# LiPo_Charger.net
KiCad netlist of a schematic drawn in Altium Designer
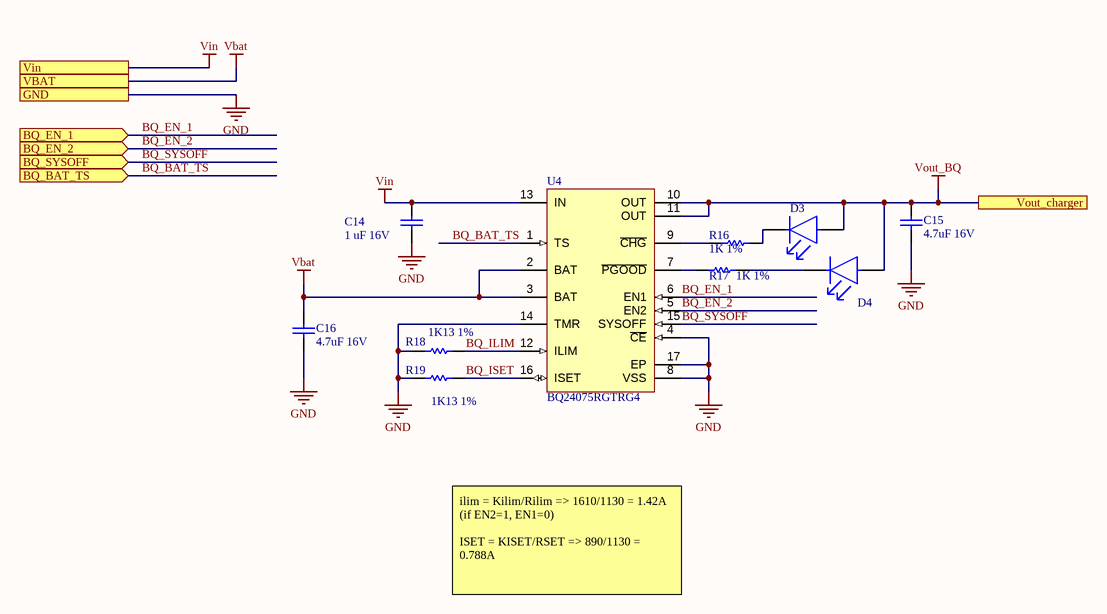
[diagram p0: LiPo_Charger.SchDoc]

(export (version "E")
  (design (tool "Eeschema 10.0.6"))
  (components
    (comp (ref "C14")
      (value "1 uF 16V")
      (footprint "CAPC1608X90X35ML15T15")
      (description "0603YC105JAT2A")
      (fields (field (name "MANUFACTURER") "AVX Interconnect / Elco"))
      (libsource (lib "Altium Content Vault") (part "CAP"))
    )
    (comp (ref "C15")
      (value "4.7uF 16V")
      (footprint "CAPC0805(2012)145_N")
      (description "CAP 4.7uF 16V -20% to +80% 0805 (2012 Metric) Thickness 1.45mm SMD")
      (fields (field (name "TOLERANCE") "-20% to +80%"))
      (libsource (lib "Altium Content Vault") (part "CAP"))
    )
    (comp (ref "C16")
      (value "4.7uF 16V")
      (footprint "CAPC0805(2012)145_N")
      (description "CAP 4.7uF 16V -20% to +80% 0805 (2012 Metric) Thickness 1.45mm SMD")
      (fields (field (name "TOLERANCE") "-20% to +80%"))
      (libsource (lib "Altium Content Vault") (part "CAP"))
    )
    (comp (ref "D3")
      (value "LTST-C170CKT")
      (footprint "FP-LTST-C170CKT-MFG")
      (description "LED RED CLEAR SMD")
      (fields (field (name "VOLTAGE") "5V"))
      (libsource (lib "Altium Content Vault") (part "8706943c75ba83719d021d2fdc84c58"))
    )
    (comp (ref "D4")
      (value "LTST-C170GKT")
      (footprint "FP-LTST-C170GKT-MFG")
      (description "LED GREEN CLEAR SMD")
      (fields (field (name "VOLTAGE") "5V"))
      (libsource (lib "Altium Content Vault") (part "8706943c75ba83719d021d2fdc84c58"))
    )
    (comp (ref "R16")
      (value "1K 1%")
      (footprint "RESC1609X50X30LL10T20")
      (description "CRCW06031K00FKEB")
      (fields (field (name "MANUFACTURER") "Vishay Dale"))
      (libsource (lib "Altium Content Vault") (part "RES"))
    )
    (comp (ref "R17")
      (value "1K 1%")
      (footprint "RESC1609X50X30LL10T20")
      (description "CRCW06031K00FKEB")
      (fields (field (name "MANUFACTURER") "Vishay Dale"))
      (libsource (lib "Altium Content Vault") (part "RES"))
    )
    (comp (ref "R18")
      (value "1K13 1%")
      (footprint "RESC0603(1608)_N")
      (description "1K13 0.1W 1% 0603 (1608 Metric)  SMD")
      (fields (field (name "POWER") "0.1 W") (field (name "TOLERANCE") "1 %"))
      (libsource (lib "Altium Content Vault") (part "RES"))
    )
    (comp (ref "R19")
      (value "1K13 1%")
      (footprint "RESC0603(1608)_N")
      (description "1K13 0.1W 1% 0603 (1608 Metric)  SMD")
      (fields (field (name "POWER") "0.1 W") (field (name "TOLERANCE") "1 %"))
      (libsource (lib "Altium Content Vault") (part "RES"))
    )
    (comp (ref "U4")
      (value "BQ24075RGTRG4")
      (footprint "RGT16-1700X1700TP")
      (fields (field (name "MANUFACTURER") "Texas Instruments"))
      (libsource (lib "Altium Content Vault") (part "TI-BQ24075RGT16-1700X1700TP"))
    )
  )
  (nets
    (net (code "1") (name "/BQ_BAT_TS") (class "Default")
      (node (ref "U4") (pin "1") (pinfunction "TS_1") (pintype "input"))
    )
    (net (code "2") (name "/BQ_EN_1") (class "Default")
      (node (ref "U4") (pin "6") (pinfunction "EN1_6") (pintype "input"))
    )
    (net (code "3") (name "/BQ_EN_2") (class "Default")
      (node (ref "U4") (pin "5") (pinfunction "EN2_5") (pintype "input"))
    )
    (net (code "4") (name "/BQ_ILIM") (class "Default")
      (node (ref "R18") (pin "2") (pinfunction "2_2") (pintype "passive"))
      (node (ref "U4") (pin "12") (pinfunction "ILIM_12") (pintype "input"))
    )
    (net (code "5") (name "/BQ_ISET") (class "Default")
      (node (ref "R19") (pin "2") (pinfunction "2_2") (pintype "passive"))
      (node (ref "U4") (pin "16") (pinfunction "ISET_16") (pintype "bidirectional"))
    )
    (net (code "6") (name "/BQ_SYSOFF") (class "Default")
      (node (ref "U4") (pin "15") (pinfunction "SYSOFF_15") (pintype "input"))
    )
    (net (code "7") (name "GND") (class "Default")
      (node (ref "C14") (pin "1") (pinfunction "1_1") (pintype "passive"))
      (node (ref "C15") (pin "1") (pinfunction "1_1") (pintype "passive"))
      (node (ref "C16") (pin "2") (pinfunction "2_2") (pintype "passive"))
      (node (ref "R18") (pin "1") (pinfunction "1_1") (pintype "passive"))
      (node (ref "R19") (pin "1") (pinfunction "1_1") (pintype "passive"))
      (node (ref "U4") (pin "14") (pinfunction "TMR_14") (pintype "passive"))
      (node (ref "U4") (pin "17") (pinfunction "EP_17") (pintype "power_in"))
      (node (ref "U4") (pin "4") (pinfunction "~{CE}_4") (pintype "input"))
      (node (ref "U4") (pin "8") (pinfunction "VSS_8") (pintype "power_in"))
    )
    (net (code "8") (name "Net-(D3-C)") (class "Default")
      (node (ref "D3") (pin "1") (pinfunction "C_1") (pintype "passive"))
      (node (ref "R16") (pin "2") (pinfunction "2_2") (pintype "passive"))
    )
    (net (code "9") (name "Net-(D4-C)") (class "Default")
      (node (ref "D4") (pin "1") (pinfunction "C_1") (pintype "passive"))
      (node (ref "R17") (pin "2") (pinfunction "2_2") (pintype "passive"))
    )
    (net (code "10") (name "Net-(U4-~{CHG})") (class "Default")
      (node (ref "R16") (pin "1") (pinfunction "1_1") (pintype "passive"))
      (node (ref "U4") (pin "9") (pinfunction "~{CHG}_9") (pintype "tri_state"))
    )
    (net (code "11") (name "Net-(U4-~{PGOOD})") (class "Default")
      (node (ref "R17") (pin "1") (pinfunction "1_1") (pintype "passive"))
      (node (ref "U4") (pin "7") (pinfunction "~{PGOOD}_7") (pintype "tri_state"))
    )
    (net (code "12") (name "Vbat") (class "Default")
      (node (ref "C16") (pin "1") (pinfunction "1_1") (pintype "passive"))
      (node (ref "U4") (pin "2") (pinfunction "BAT_2") (pintype "power_in"))
      (node (ref "U4") (pin "3") (pinfunction "BAT_3") (pintype "power_in"))
    )
    (net (code "13") (name "Vin") (class "Default")
      (node (ref "C14") (pin "2") (pinfunction "2_2") (pintype "passive"))
      (node (ref "U4") (pin "13") (pinfunction "IN_13") (pintype "power_in"))
    )
    (net (code "14") (name "Vout_BQ") (class "Default")
      (node (ref "C15") (pin "2") (pinfunction "2_2") (pintype "passive"))
      (node (ref "D3") (pin "2") (pinfunction "A_2") (pintype "passive"))
      (node (ref "D4") (pin "2") (pinfunction "A_2") (pintype "passive"))
      (node (ref "U4") (pin "10") (pinfunction "OUT_10") (pintype "power_in"))
      (node (ref "U4") (pin "11") (pinfunction "OUT_11") (pintype "power_in"))
    )
  )
)
